# SolarBoard_version_2_01.net
KiCad netlist of a schematic drawn in EAGLE
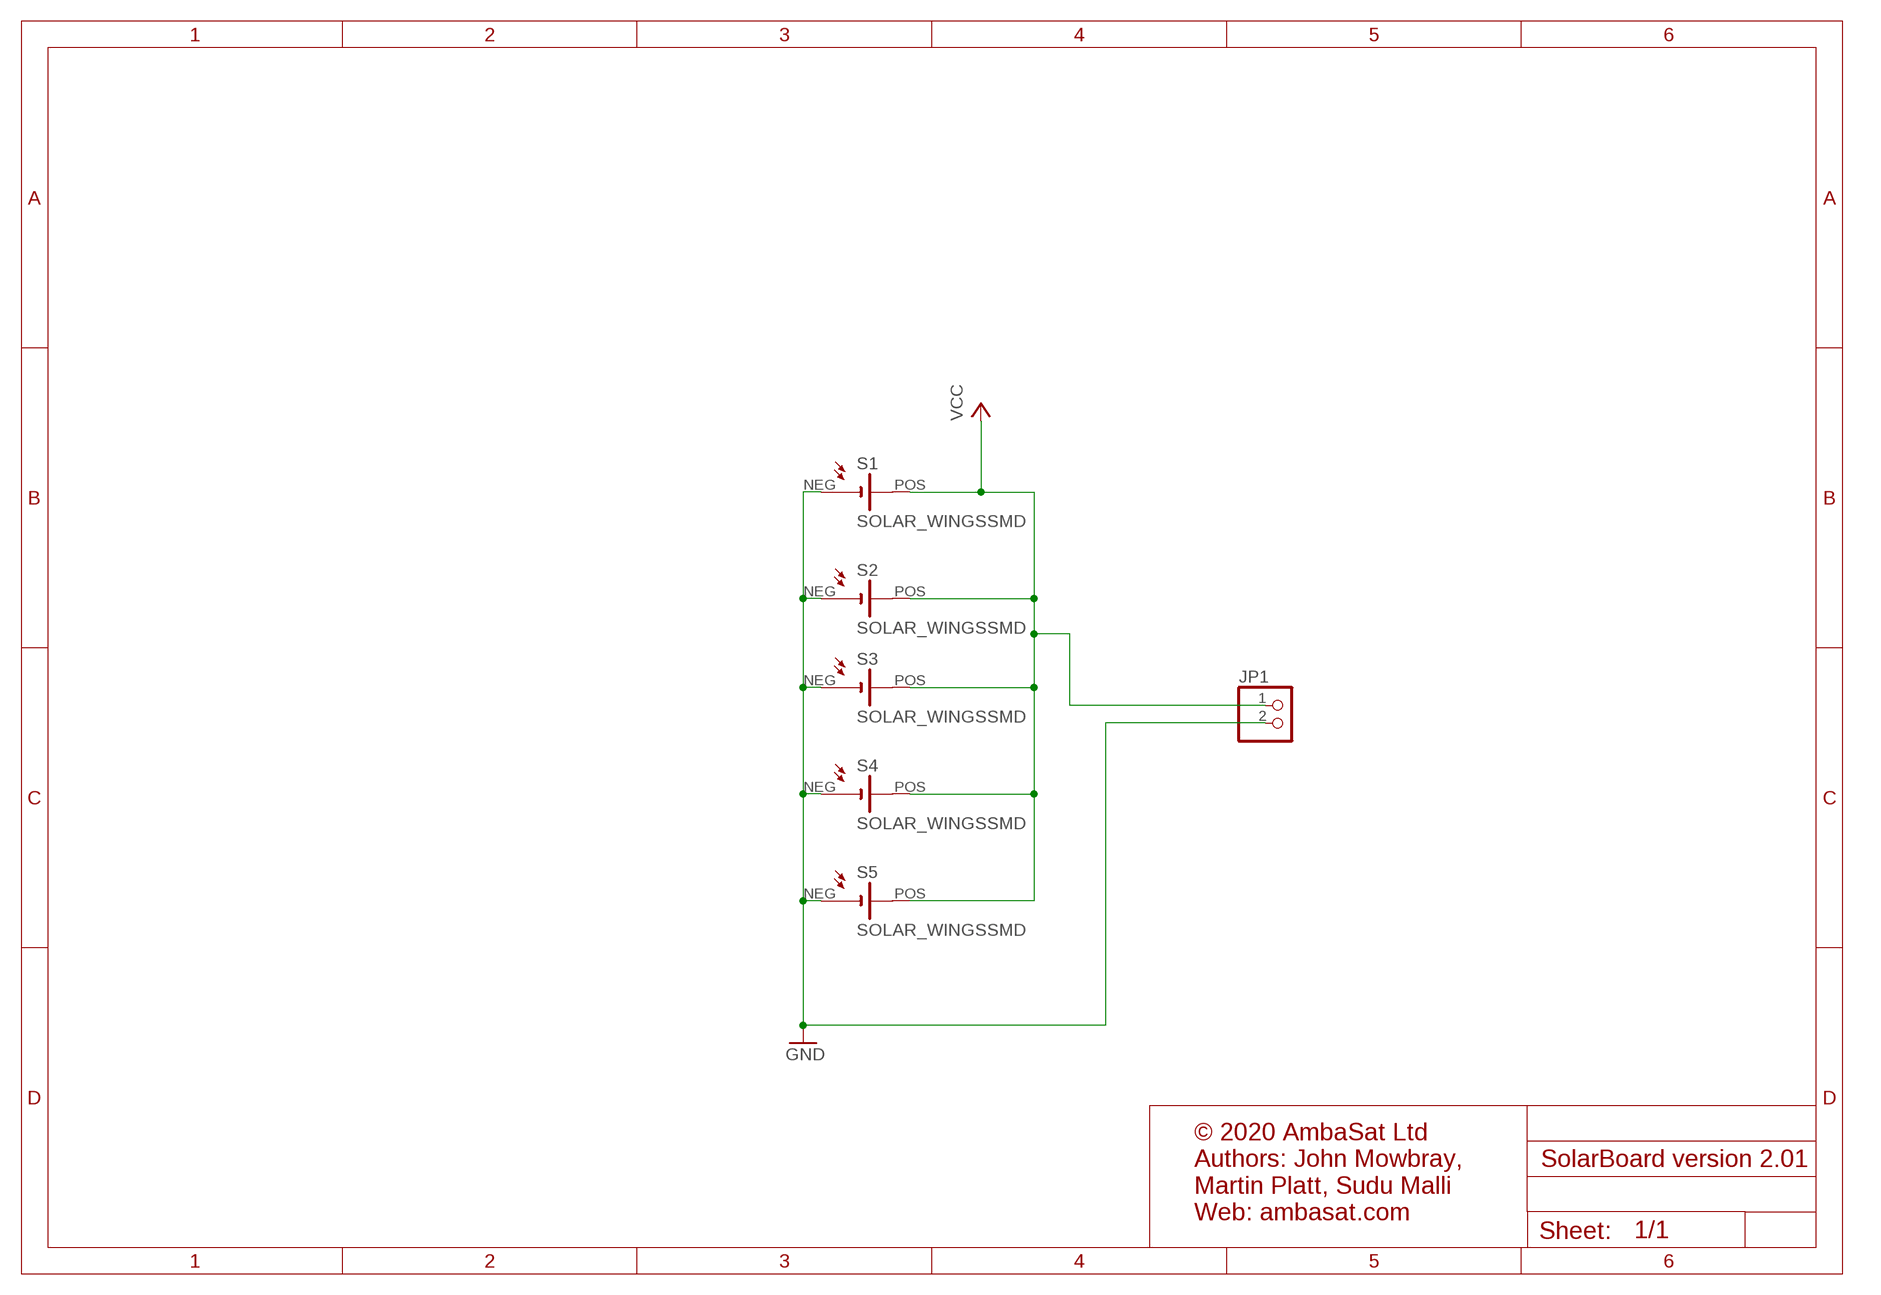
[diagram p0: schematic, sheet 1]

(export (version "E")
  (design (tool "Eeschema 10.0.6"))
  (components
    (comp (ref "JP1")
      (value "PINHD-1X2")
      (footprint "eagle-import:1X02")
      (libsource (lib "eagle-import") (part "PINHD-1X2"))
    )
    (comp (ref "S1")
      (value "SOLAR_WINGSSMD")
      (footprint "eagle-import:SOLAR_WINGS_SMD")
      (libsource (lib "eagle-import") (part "SOLAR_WINGSSMD"))
    )
    (comp (ref "S2")
      (value "SOLAR_WINGSSMD")
      (footprint "eagle-import:SOLAR_WINGS_SMD")
      (libsource (lib "eagle-import") (part "SOLAR_WINGSSMD"))
    )
    (comp (ref "S3")
      (value "SOLAR_WINGSSMD")
      (footprint "eagle-import:SOLAR_WINGS_SMD")
      (libsource (lib "eagle-import") (part "SOLAR_WINGSSMD"))
    )
    (comp (ref "S4")
      (value "SOLAR_WINGSSMD")
      (footprint "eagle-import:SOLAR_WINGS_SMD")
      (libsource (lib "eagle-import") (part "SOLAR_WINGSSMD"))
    )
    (comp (ref "S5")
      (value "SOLAR_WINGSSMD")
      (footprint "eagle-import:SOLAR_WINGS_SMD")
      (libsource (lib "eagle-import") (part "SOLAR_WINGSSMD"))
    )
  )
  (nets
    (net (code "1") (name "GND") (class "Default")
      (node (ref "JP1") (pin "2") (pinfunction "2_2") (pintype "passive"))
      (node (ref "S1") (pin "NEG") (pinfunction "NEG_NEG") (pintype "bidirectional"))
      (node (ref "S2") (pin "NEG") (pinfunction "NEG_NEG") (pintype "bidirectional"))
      (node (ref "S3") (pin "NEG") (pinfunction "NEG_NEG") (pintype "bidirectional"))
      (node (ref "S4") (pin "NEG") (pinfunction "NEG_NEG") (pintype "bidirectional"))
      (node (ref "S5") (pin "NEG") (pinfunction "NEG_NEG") (pintype "bidirectional"))
    )
    (net (code "2") (name "VCC") (class "Default")
      (node (ref "JP1") (pin "1") (pinfunction "1_1") (pintype "passive"))
      (node (ref "S1") (pin "POS") (pinfunction "POS_POS") (pintype "bidirectional"))
      (node (ref "S2") (pin "POS") (pinfunction "POS_POS") (pintype "bidirectional"))
      (node (ref "S3") (pin "POS") (pinfunction "POS_POS") (pintype "bidirectional"))
      (node (ref "S4") (pin "POS") (pinfunction "POS_POS") (pintype "bidirectional"))
      (node (ref "S5") (pin "POS") (pinfunction "POS_POS") (pintype "bidirectional"))
    )
  )
)
